# MDmotherboard.net
KiCad netlist of a schematic drawn in EAGLE
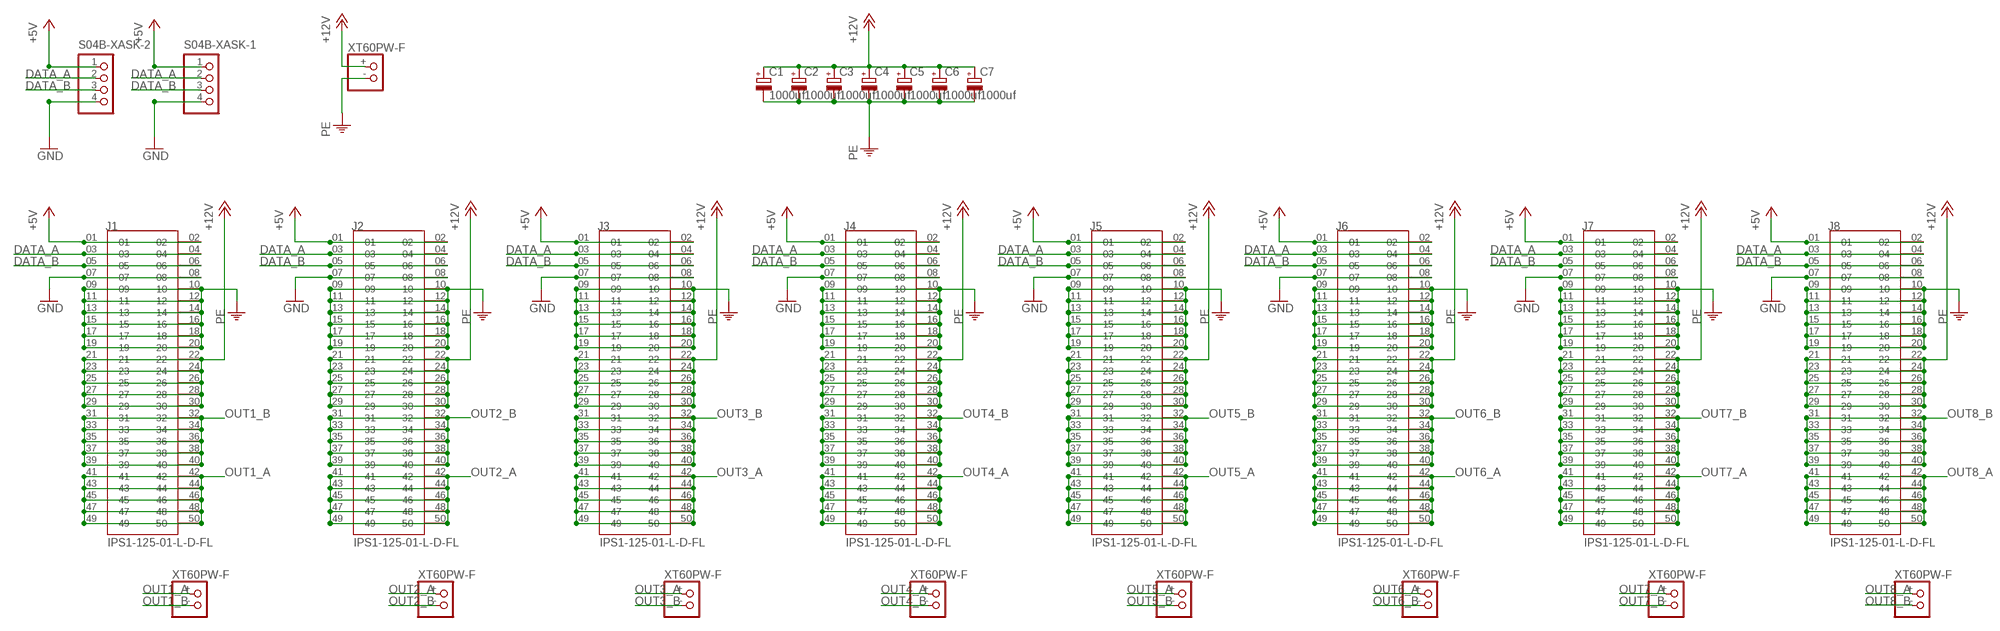
[diagram p0: schematic, sheet 1]

(export (version "E")
  (design (tool "Eeschema 10.0.6"))
  (components
    (comp (ref "C1")
      (value "1000uf")
      (footprint "eagle-import:E3,5-10")
      (libsource (lib "eagle-import") (part "CPOL-EUE3.5-10"))
    )
    (comp (ref "C2")
      (value "1000uf")
      (footprint "eagle-import:E3,5-10")
      (libsource (lib "eagle-import") (part "CPOL-EUE3.5-10"))
    )
    (comp (ref "C3")
      (value "1000uf")
      (footprint "eagle-import:E3,5-10")
      (libsource (lib "eagle-import") (part "CPOL-EUE3.5-10"))
    )
    (comp (ref "C4")
      (value "1000uf")
      (footprint "eagle-import:E3,5-10")
      (libsource (lib "eagle-import") (part "CPOL-EUE3.5-10"))
    )
    (comp (ref "C5")
      (value "1000uf")
      (footprint "eagle-import:E3,5-10")
      (libsource (lib "eagle-import") (part "CPOL-EUE3.5-10"))
    )
    (comp (ref "C6")
      (value "1000uf")
      (footprint "eagle-import:E3,5-10")
      (libsource (lib "eagle-import") (part "CPOL-EUE3.5-10"))
    )
    (comp (ref "C7")
      (value "1000uf")
      (footprint "eagle-import:E3,5-10")
      (libsource (lib "eagle-import") (part "CPOL-EUE3.5-10"))
    )
    (comp (ref "J1")
      (value "IPS1-125-01-L-D-FL")
      (footprint "eagle-import:SAMTEC_IPS1-125-01-L-D-FL")
      (fields (field (name "MF") "Samtec Inc."))
      (libsource (lib "eagle-import") (part "IPS1-125-01-L-D-FL"))
    )
    (comp (ref "J2")
      (value "IPS1-125-01-L-D-FL")
      (footprint "eagle-import:SAMTEC_IPS1-125-01-L-D-FL")
      (fields (field (name "MF") "Samtec Inc."))
      (libsource (lib "eagle-import") (part "IPS1-125-01-L-D-FL"))
    )
    (comp (ref "J3")
      (value "IPS1-125-01-L-D-FL")
      (footprint "eagle-import:SAMTEC_IPS1-125-01-L-D-FL")
      (fields (field (name "MF") "Samtec Inc."))
      (libsource (lib "eagle-import") (part "IPS1-125-01-L-D-FL"))
    )
    (comp (ref "J4")
      (value "IPS1-125-01-L-D-FL")
      (footprint "eagle-import:SAMTEC_IPS1-125-01-L-D-FL")
      (fields (field (name "MF") "Samtec Inc."))
      (libsource (lib "eagle-import") (part "IPS1-125-01-L-D-FL"))
    )
    (comp (ref "J5")
      (value "IPS1-125-01-L-D-FL")
      (footprint "eagle-import:SAMTEC_IPS1-125-01-L-D-FL")
      (fields (field (name "MF") "Samtec Inc."))
      (libsource (lib "eagle-import") (part "IPS1-125-01-L-D-FL"))
    )
    (comp (ref "J6")
      (value "IPS1-125-01-L-D-FL")
      (footprint "eagle-import:SAMTEC_IPS1-125-01-L-D-FL")
      (fields (field (name "MF") "Samtec Inc."))
      (libsource (lib "eagle-import") (part "IPS1-125-01-L-D-FL"))
    )
    (comp (ref "J7")
      (value "IPS1-125-01-L-D-FL")
      (footprint "eagle-import:SAMTEC_IPS1-125-01-L-D-FL")
      (fields (field (name "MF") "Samtec Inc."))
      (libsource (lib "eagle-import") (part "IPS1-125-01-L-D-FL"))
    )
    (comp (ref "J8")
      (value "IPS1-125-01-L-D-FL")
      (footprint "eagle-import:SAMTEC_IPS1-125-01-L-D-FL")
      (fields (field (name "MF") "Samtec Inc."))
      (libsource (lib "eagle-import") (part "IPS1-125-01-L-D-FL"))
    )
    (comp (ref "S04B-XASK-1")
      (value "S4B-XASK-1")
      (footprint "eagle-import:S4B-XASK-1")
      (libsource (lib "eagle-import") (part "S4B-XASK-1"))
    )
    (comp (ref "S04B-XASK-2")
      (value "S4B-XASK-1")
      (footprint "eagle-import:S4B-XASK-1")
      (libsource (lib "eagle-import") (part "S4B-XASK-1"))
    )
    (comp (ref "U$1")
      (value "XT60PW-F")
      (footprint "eagle-import:XT60PW-F")
      (libsource (lib "eagle-import") (part "XT60PW-F"))
    )
    (comp (ref "U$2")
      (value "XT60PW-F")
      (footprint "eagle-import:XT60PW-F")
      (libsource (lib "eagle-import") (part "XT60PW-F"))
    )
    (comp (ref "U$3")
      (value "XT60PW-F")
      (footprint "eagle-import:XT60PW-F")
      (libsource (lib "eagle-import") (part "XT60PW-F"))
    )
    (comp (ref "U$4")
      (value "XT60PW-F")
      (footprint "eagle-import:XT60PW-F")
      (libsource (lib "eagle-import") (part "XT60PW-F"))
    )
    (comp (ref "U$5")
      (value "XT60PW-F")
      (footprint "eagle-import:XT60PW-F")
      (libsource (lib "eagle-import") (part "XT60PW-F"))
    )
    (comp (ref "U$6")
      (value "XT60PW-F")
      (footprint "eagle-import:XT60PW-F")
      (libsource (lib "eagle-import") (part "XT60PW-F"))
    )
    (comp (ref "U$7")
      (value "XT60PW-F")
      (footprint "eagle-import:XT60PW-F")
      (libsource (lib "eagle-import") (part "XT60PW-F"))
    )
    (comp (ref "U$8")
      (value "XT60PW-F")
      (footprint "eagle-import:XT60PW-F")
      (libsource (lib "eagle-import") (part "XT60PW-F"))
    )
    (comp (ref "U$9")
      (value "XT60PW-F")
      (footprint "eagle-import:XT60PW-F")
      (libsource (lib "eagle-import") (part "XT60PW-F"))
    )
  )
  (nets
    (net (code "1") (name "+5V") (class "Default")
      (node (ref "J1") (pin "01") (pinfunction "01_01") (pintype "passive"))
      (node (ref "J1") (pin "02") (pinfunction "02_02") (pintype "passive"))
      (node (ref "J2") (pin "01") (pinfunction "01_01") (pintype "passive"))
      (node (ref "J2") (pin "02") (pinfunction "02_02") (pintype "passive"))
      (node (ref "J3") (pin "01") (pinfunction "01_01") (pintype "passive"))
      (node (ref "J3") (pin "02") (pinfunction "02_02") (pintype "passive"))
      (node (ref "J4") (pin "01") (pinfunction "01_01") (pintype "passive"))
      (node (ref "J4") (pin "02") (pinfunction "02_02") (pintype "passive"))
      (node (ref "J5") (pin "01") (pinfunction "01_01") (pintype "passive"))
      (node (ref "J5") (pin "02") (pinfunction "02_02") (pintype "passive"))
      (node (ref "J6") (pin "01") (pinfunction "01_01") (pintype "passive"))
      (node (ref "J6") (pin "02") (pinfunction "02_02") (pintype "passive"))
      (node (ref "J7") (pin "01") (pinfunction "01_01") (pintype "passive"))
      (node (ref "J7") (pin "02") (pinfunction "02_02") (pintype "passive"))
      (node (ref "J8") (pin "01") (pinfunction "01_01") (pintype "passive"))
      (node (ref "J8") (pin "02") (pinfunction "02_02") (pintype "passive"))
      (node (ref "S04B-XASK-1") (pin "1") (pinfunction "1_1") (pintype "passive"))
      (node (ref "S04B-XASK-2") (pin "1") (pinfunction "1_1") (pintype "passive"))
    )
    (net (code "2") (name "+12V") (class "Default")
      (node (ref "C1") (pin "+") (pinfunction "+_+") (pintype "passive"))
      (node (ref "C2") (pin "+") (pinfunction "+_+") (pintype "passive"))
      (node (ref "C3") (pin "+") (pinfunction "+_+") (pintype "passive"))
      (node (ref "C4") (pin "+") (pinfunction "+_+") (pintype "passive"))
      (node (ref "C5") (pin "+") (pinfunction "+_+") (pintype "passive"))
      (node (ref "C6") (pin "+") (pinfunction "+_+") (pintype "passive"))
      (node (ref "C7") (pin "+") (pinfunction "+_+") (pintype "passive"))
      (node (ref "J1") (pin "21") (pinfunction "21_21") (pintype "passive"))
      (node (ref "J1") (pin "22") (pinfunction "22_22") (pintype "passive"))
      (node (ref "J1") (pin "23") (pinfunction "23_23") (pintype "passive"))
      (node (ref "J1") (pin "24") (pinfunction "24_24") (pintype "passive"))
      (node (ref "J1") (pin "25") (pinfunction "25_25") (pintype "passive"))
      (node (ref "J1") (pin "26") (pinfunction "26_26") (pintype "passive"))
      (node (ref "J1") (pin "27") (pinfunction "27_27") (pintype "passive"))
      (node (ref "J1") (pin "28") (pinfunction "28_28") (pintype "passive"))
      (node (ref "J1") (pin "29") (pinfunction "29_29") (pintype "passive"))
      (node (ref "J1") (pin "30") (pinfunction "30_30") (pintype "passive"))
      (node (ref "J2") (pin "21") (pinfunction "21_21") (pintype "passive"))
      (node (ref "J2") (pin "22") (pinfunction "22_22") (pintype "passive"))
      (node (ref "J2") (pin "23") (pinfunction "23_23") (pintype "passive"))
      (node (ref "J2") (pin "24") (pinfunction "24_24") (pintype "passive"))
      (node (ref "J2") (pin "25") (pinfunction "25_25") (pintype "passive"))
      (node (ref "J2") (pin "26") (pinfunction "26_26") (pintype "passive"))
      (node (ref "J2") (pin "27") (pinfunction "27_27") (pintype "passive"))
      (node (ref "J2") (pin "28") (pinfunction "28_28") (pintype "passive"))
      (node (ref "J2") (pin "29") (pinfunction "29_29") (pintype "passive"))
      (node (ref "J2") (pin "30") (pinfunction "30_30") (pintype "passive"))
      (node (ref "J3") (pin "21") (pinfunction "21_21") (pintype "passive"))
      (node (ref "J3") (pin "22") (pinfunction "22_22") (pintype "passive"))
      (node (ref "J3") (pin "23") (pinfunction "23_23") (pintype "passive"))
      (node (ref "J3") (pin "24") (pinfunction "24_24") (pintype "passive"))
      (node (ref "J3") (pin "25") (pinfunction "25_25") (pintype "passive"))
      (node (ref "J3") (pin "26") (pinfunction "26_26") (pintype "passive"))
      (node (ref "J3") (pin "27") (pinfunction "27_27") (pintype "passive"))
      (node (ref "J3") (pin "28") (pinfunction "28_28") (pintype "passive"))
      (node (ref "J3") (pin "29") (pinfunction "29_29") (pintype "passive"))
      (node (ref "J3") (pin "30") (pinfunction "30_30") (pintype "passive"))
      (node (ref "J4") (pin "21") (pinfunction "21_21") (pintype "passive"))
      (node (ref "J4") (pin "22") (pinfunction "22_22") (pintype "passive"))
      (node (ref "J4") (pin "23") (pinfunction "23_23") (pintype "passive"))
      (node (ref "J4") (pin "24") (pinfunction "24_24") (pintype "passive"))
      (node (ref "J4") (pin "25") (pinfunction "25_25") (pintype "passive"))
      (node (ref "J4") (pin "26") (pinfunction "26_26") (pintype "passive"))
      (node (ref "J4") (pin "27") (pinfunction "27_27") (pintype "passive"))
      (node (ref "J4") (pin "28") (pinfunction "28_28") (pintype "passive"))
      (node (ref "J4") (pin "29") (pinfunction "29_29") (pintype "passive"))
      (node (ref "J4") (pin "30") (pinfunction "30_30") (pintype "passive"))
      (node (ref "J5") (pin "21") (pinfunction "21_21") (pintype "passive"))
      (node (ref "J5") (pin "22") (pinfunction "22_22") (pintype "passive"))
      (node (ref "J5") (pin "23") (pinfunction "23_23") (pintype "passive"))
      (node (ref "J5") (pin "24") (pinfunction "24_24") (pintype "passive"))
      (node (ref "J5") (pin "25") (pinfunction "25_25") (pintype "passive"))
      (node (ref "J5") (pin "26") (pinfunction "26_26") (pintype "passive"))
      (node (ref "J5") (pin "27") (pinfunction "27_27") (pintype "passive"))
      (node (ref "J5") (pin "28") (pinfunction "28_28") (pintype "passive"))
      (node (ref "J5") (pin "29") (pinfunction "29_29") (pintype "passive"))
      (node (ref "J5") (pin "30") (pinfunction "30_30") (pintype "passive"))
      (node (ref "J6") (pin "21") (pinfunction "21_21") (pintype "passive"))
      (node (ref "J6") (pin "22") (pinfunction "22_22") (pintype "passive"))
      (node (ref "J6") (pin "23") (pinfunction "23_23") (pintype "passive"))
      (node (ref "J6") (pin "24") (pinfunction "24_24") (pintype "passive"))
      (node (ref "J6") (pin "25") (pinfunction "25_25") (pintype "passive"))
      (node (ref "J6") (pin "26") (pinfunction "26_26") (pintype "passive"))
      (node (ref "J6") (pin "27") (pinfunction "27_27") (pintype "passive"))
      (node (ref "J6") (pin "28") (pinfunction "28_28") (pintype "passive"))
      (node (ref "J6") (pin "29") (pinfunction "29_29") (pintype "passive"))
      (node (ref "J6") (pin "30") (pinfunction "30_30") (pintype "passive"))
      (node (ref "J7") (pin "21") (pinfunction "21_21") (pintype "passive"))
      (node (ref "J7") (pin "22") (pinfunction "22_22") (pintype "passive"))
      (node (ref "J7") (pin "23") (pinfunction "23_23") (pintype "passive"))
      (node (ref "J7") (pin "24") (pinfunction "24_24") (pintype "passive"))
      (node (ref "J7") (pin "25") (pinfunction "25_25") (pintype "passive"))
      (node (ref "J7") (pin "26") (pinfunction "26_26") (pintype "passive"))
      (node (ref "J7") (pin "27") (pinfunction "27_27") (pintype "passive"))
      (node (ref "J7") (pin "28") (pinfunction "28_28") (pintype "passive"))
      (node (ref "J7") (pin "29") (pinfunction "29_29") (pintype "passive"))
      (node (ref "J7") (pin "30") (pinfunction "30_30") (pintype "passive"))
      (node (ref "J8") (pin "21") (pinfunction "21_21") (pintype "passive"))
      (node (ref "J8") (pin "22") (pinfunction "22_22") (pintype "passive"))
      (node (ref "J8") (pin "23") (pinfunction "23_23") (pintype "passive"))
      (node (ref "J8") (pin "24") (pinfunction "24_24") (pintype "passive"))
      (node (ref "J8") (pin "25") (pinfunction "25_25") (pintype "passive"))
      (node (ref "J8") (pin "26") (pinfunction "26_26") (pintype "passive"))
      (node (ref "J8") (pin "27") (pinfunction "27_27") (pintype "passive"))
      (node (ref "J8") (pin "28") (pinfunction "28_28") (pintype "passive"))
      (node (ref "J8") (pin "29") (pinfunction "29_29") (pintype "passive"))
      (node (ref "J8") (pin "30") (pinfunction "30_30") (pintype "passive"))
      (node (ref "U$1") (pin "+") (pinfunction "+_+") (pintype "passive"))
    )
    (net (code "3") (name "/DATA_A") (class "Default")
      (node (ref "J1") (pin "03") (pinfunction "03_03") (pintype "passive"))
      (node (ref "J1") (pin "04") (pinfunction "04_04") (pintype "passive"))
      (node (ref "J2") (pin "03") (pinfunction "03_03") (pintype "passive"))
      (node (ref "J2") (pin "04") (pinfunction "04_04") (pintype "passive"))
      (node (ref "J3") (pin "03") (pinfunction "03_03") (pintype "passive"))
      (node (ref "J3") (pin "04") (pinfunction "04_04") (pintype "passive"))
      (node (ref "J4") (pin "03") (pinfunction "03_03") (pintype "passive"))
      (node (ref "J4") (pin "04") (pinfunction "04_04") (pintype "passive"))
      (node (ref "J5") (pin "03") (pinfunction "03_03") (pintype "passive"))
      (node (ref "J5") (pin "04") (pinfunction "04_04") (pintype "passive"))
      (node (ref "J6") (pin "03") (pinfunction "03_03") (pintype "passive"))
      (node (ref "J6") (pin "04") (pinfunction "04_04") (pintype "passive"))
      (node (ref "J7") (pin "03") (pinfunction "03_03") (pintype "passive"))
      (node (ref "J7") (pin "04") (pinfunction "04_04") (pintype "passive"))
      (node (ref "J8") (pin "03") (pinfunction "03_03") (pintype "passive"))
      (node (ref "J8") (pin "04") (pinfunction "04_04") (pintype "passive"))
      (node (ref "S04B-XASK-1") (pin "2") (pinfunction "2_2") (pintype "passive"))
      (node (ref "S04B-XASK-2") (pin "2") (pinfunction "2_2") (pintype "passive"))
    )
    (net (code "4") (name "/DATA_B") (class "Default")
      (node (ref "J1") (pin "05") (pinfunction "05_05") (pintype "passive"))
      (node (ref "J1") (pin "06") (pinfunction "06_06") (pintype "passive"))
      (node (ref "J2") (pin "05") (pinfunction "05_05") (pintype "passive"))
      (node (ref "J2") (pin "06") (pinfunction "06_06") (pintype "passive"))
      (node (ref "J3") (pin "05") (pinfunction "05_05") (pintype "passive"))
      (node (ref "J3") (pin "06") (pinfunction "06_06") (pintype "passive"))
      (node (ref "J4") (pin "05") (pinfunction "05_05") (pintype "passive"))
      (node (ref "J4") (pin "06") (pinfunction "06_06") (pintype "passive"))
      (node (ref "J5") (pin "05") (pinfunction "05_05") (pintype "passive"))
      (node (ref "J5") (pin "06") (pinfunction "06_06") (pintype "passive"))
      (node (ref "J6") (pin "05") (pinfunction "05_05") (pintype "passive"))
      (node (ref "J6") (pin "06") (pinfunction "06_06") (pintype "passive"))
      (node (ref "J7") (pin "05") (pinfunction "05_05") (pintype "passive"))
      (node (ref "J7") (pin "06") (pinfunction "06_06") (pintype "passive"))
      (node (ref "J8") (pin "05") (pinfunction "05_05") (pintype "passive"))
      (node (ref "J8") (pin "06") (pinfunction "06_06") (pintype "passive"))
      (node (ref "S04B-XASK-1") (pin "3") (pinfunction "3_3") (pintype "passive"))
      (node (ref "S04B-XASK-2") (pin "3") (pinfunction "3_3") (pintype "passive"))
    )
    (net (code "5") (name "/OUT1_A") (class "Default")
      (node (ref "J1") (pin "41") (pinfunction "41_41") (pintype "passive"))
      (node (ref "J1") (pin "42") (pinfunction "42_42") (pintype "passive"))
      (node (ref "J1") (pin "43") (pinfunction "43_43") (pintype "passive"))
      (node (ref "J1") (pin "44") (pinfunction "44_44") (pintype "passive"))
      (node (ref "J1") (pin "45") (pinfunction "45_45") (pintype "passive"))
      (node (ref "J1") (pin "46") (pinfunction "46_46") (pintype "passive"))
      (node (ref "J1") (pin "47") (pinfunction "47_47") (pintype "passive"))
      (node (ref "J1") (pin "48") (pinfunction "48_48") (pintype "passive"))
      (node (ref "J1") (pin "49") (pinfunction "49_49") (pintype "passive"))
      (node (ref "J1") (pin "50") (pinfunction "50_50") (pintype "passive"))
      (node (ref "U$2") (pin "+") (pinfunction "+_+") (pintype "passive"))
    )
    (net (code "6") (name "/OUT1_B") (class "Default")
      (node (ref "J1") (pin "31") (pinfunction "31_31") (pintype "passive"))
      (node (ref "J1") (pin "32") (pinfunction "32_32") (pintype "passive"))
      (node (ref "J1") (pin "33") (pinfunction "33_33") (pintype "passive"))
      (node (ref "J1") (pin "34") (pinfunction "34_34") (pintype "passive"))
      (node (ref "J1") (pin "35") (pinfunction "35_35") (pintype "passive"))
      (node (ref "J1") (pin "36") (pinfunction "36_36") (pintype "passive"))
      (node (ref "J1") (pin "37") (pinfunction "37_37") (pintype "passive"))
      (node (ref "J1") (pin "38") (pinfunction "38_38") (pintype "passive"))
      (node (ref "J1") (pin "39") (pinfunction "39_39") (pintype "passive"))
      (node (ref "J1") (pin "40") (pinfunction "40_40") (pintype "passive"))
      (node (ref "U$2") (pin "-") (pinfunction "-_-") (pintype "passive"))
    )
    (net (code "7") (name "/OUT2_A") (class "Default")
      (node (ref "J2") (pin "41") (pinfunction "41_41") (pintype "passive"))
      (node (ref "J2") (pin "42") (pinfunction "42_42") (pintype "passive"))
      (node (ref "J2") (pin "43") (pinfunction "43_43") (pintype "passive"))
      (node (ref "J2") (pin "44") (pinfunction "44_44") (pintype "passive"))
      (node (ref "J2") (pin "45") (pinfunction "45_45") (pintype "passive"))
      (node (ref "J2") (pin "46") (pinfunction "46_46") (pintype "passive"))
      (node (ref "J2") (pin "47") (pinfunction "47_47") (pintype "passive"))
      (node (ref "J2") (pin "48") (pinfunction "48_48") (pintype "passive"))
      (node (ref "J2") (pin "49") (pinfunction "49_49") (pintype "passive"))
      (node (ref "J2") (pin "50") (pinfunction "50_50") (pintype "passive"))
      (node (ref "U$3") (pin "+") (pinfunction "+_+") (pintype "passive"))
    )
    (net (code "8") (name "/OUT2_B") (class "Default")
      (node (ref "J2") (pin "31") (pinfunction "31_31") (pintype "passive"))
      (node (ref "J2") (pin "32") (pinfunction "32_32") (pintype "passive"))
      (node (ref "J2") (pin "33") (pinfunction "33_33") (pintype "passive"))
      (node (ref "J2") (pin "34") (pinfunction "34_34") (pintype "passive"))
      (node (ref "J2") (pin "35") (pinfunction "35_35") (pintype "passive"))
      (node (ref "J2") (pin "36") (pinfunction "36_36") (pintype "passive"))
      (node (ref "J2") (pin "37") (pinfunction "37_37") (pintype "passive"))
      (node (ref "J2") (pin "38") (pinfunction "38_38") (pintype "passive"))
      (node (ref "J2") (pin "39") (pinfunction "39_39") (pintype "passive"))
      (node (ref "J2") (pin "40") (pinfunction "40_40") (pintype "passive"))
      (node (ref "U$3") (pin "-") (pinfunction "-_-") (pintype "passive"))
    )
    (net (code "9") (name "/OUT3_A") (class "Default")
      (node (ref "J3") (pin "41") (pinfunction "41_41") (pintype "passive"))
      (node (ref "J3") (pin "42") (pinfunction "42_42") (pintype "passive"))
      (node (ref "J3") (pin "43") (pinfunction "43_43") (pintype "passive"))
      (node (ref "J3") (pin "44") (pinfunction "44_44") (pintype "passive"))
      (node (ref "J3") (pin "45") (pinfunction "45_45") (pintype "passive"))
      (node (ref "J3") (pin "46") (pinfunction "46_46") (pintype "passive"))
      (node (ref "J3") (pin "47") (pinfunction "47_47") (pintype "passive"))
      (node (ref "J3") (pin "48") (pinfunction "48_48") (pintype "passive"))
      (node (ref "J3") (pin "49") (pinfunction "49_49") (pintype "passive"))
      (node (ref "J3") (pin "50") (pinfunction "50_50") (pintype "passive"))
      (node (ref "U$4") (pin "+") (pinfunction "+_+") (pintype "passive"))
    )
    (net (code "10") (name "/OUT3_B") (class "Default")
      (node (ref "J3") (pin "31") (pinfunction "31_31") (pintype "passive"))
      (node (ref "J3") (pin "32") (pinfunction "32_32") (pintype "passive"))
      (node (ref "J3") (pin "33") (pinfunction "33_33") (pintype "passive"))
      (node (ref "J3") (pin "34") (pinfunction "34_34") (pintype "passive"))
      (node (ref "J3") (pin "35") (pinfunction "35_35") (pintype "passive"))
      (node (ref "J3") (pin "36") (pinfunction "36_36") (pintype "passive"))
      (node (ref "J3") (pin "37") (pinfunction "37_37") (pintype "passive"))
      (node (ref "J3") (pin "38") (pinfunction "38_38") (pintype "passive"))
      (node (ref "J3") (pin "39") (pinfunction "39_39") (pintype "passive"))
      (node (ref "J3") (pin "40") (pinfunction "40_40") (pintype "passive"))
      (node (ref "U$4") (pin "-") (pinfunction "-_-") (pintype "passive"))
    )
    (net (code "11") (name "/OUT4_A") (class "Default")
      (node (ref "J4") (pin "41") (pinfunction "41_41") (pintype "passive"))
      (node (ref "J4") (pin "42") (pinfunction "42_42") (pintype "passive"))
      (node (ref "J4") (pin "43") (pinfunction "43_43") (pintype "passive"))
      (node (ref "J4") (pin "44") (pinfunction "44_44") (pintype "passive"))
      (node (ref "J4") (pin "45") (pinfunction "45_45") (pintype "passive"))
      (node (ref "J4") (pin "46") (pinfunction "46_46") (pintype "passive"))
      (node (ref "J4") (pin "47") (pinfunction "47_47") (pintype "passive"))
      (node (ref "J4") (pin "48") (pinfunction "48_48") (pintype "passive"))
      (node (ref "J4") (pin "49") (pinfunction "49_49") (pintype "passive"))
      (node (ref "J4") (pin "50") (pinfunction "50_50") (pintype "passive"))
      (node (ref "U$5") (pin "+") (pinfunction "+_+") (pintype "passive"))
    )
    (net (code "12") (name "/OUT4_B") (class "Default")
      (node (ref "J4") (pin "31") (pinfunction "31_31") (pintype "passive"))
      (node (ref "J4") (pin "32") (pinfunction "32_32") (pintype "passive"))
      (node (ref "J4") (pin "33") (pinfunction "33_33") (pintype "passive"))
      (node (ref "J4") (pin "34") (pinfunction "34_34") (pintype "passive"))
      (node (ref "J4") (pin "35") (pinfunction "35_35") (pintype "passive"))
      (node (ref "J4") (pin "36") (pinfunction "36_36") (pintype "passive"))
      (node (ref "J4") (pin "37") (pinfunction "37_37") (pintype "passive"))
      (node (ref "J4") (pin "38") (pinfunction "38_38") (pintype "passive"))
      (node (ref "J4") (pin "39") (pinfunction "39_39") (pintype "passive"))
      (node (ref "J4") (pin "40") (pinfunction "40_40") (pintype "passive"))
      (node (ref "U$5") (pin "-") (pinfunction "-_-") (pintype "passive"))
    )
    (net (code "13") (name "/OUT5_A") (class "Default")
      (node (ref "J5") (pin "41") (pinfunction "41_41") (pintype "passive"))
      (node (ref "J5") (pin "42") (pinfunction "42_42") (pintype "passive"))
      (node (ref "J5") (pin "43") (pinfunction "43_43") (pintype "passive"))
      (node (ref "J5") (pin "44") (pinfunction "44_44") (pintype "passive"))
      (node (ref "J5") (pin "45") (pinfunction "45_45") (pintype "passive"))
      (node (ref "J5") (pin "46") (pinfunction "46_46") (pintype "passive"))
      (node (ref "J5") (pin "47") (pinfunction "47_47") (pintype "passive"))
      (node (ref "J5") (pin "48") (pinfunction "48_48") (pintype "passive"))
      (node (ref "J5") (pin "49") (pinfunction "49_49") (pintype "passive"))
      (node (ref "J5") (pin "50") (pinfunction "50_50") (pintype "passive"))
      (node (ref "U$6") (pin "+") (pinfunction "+_+") (pintype "passive"))
    )
    (net (code "14") (name "/OUT5_B") (class "Default")
      (node (ref "J5") (pin "31") (pinfunction "31_31") (pintype "passive"))
      (node (ref "J5") (pin "32") (pinfunction "32_32") (pintype "passive"))
      (node (ref "J5") (pin "33") (pinfunction "33_33") (pintype "passive"))
      (node (ref "J5") (pin "34") (pinfunction "34_34") (pintype "passive"))
      (node (ref "J5") (pin "35") (pinfunction "35_35") (pintype "passive"))
      (node (ref "J5") (pin "36") (pinfunction "36_36") (pintype "passive"))
      (node (ref "J5") (pin "37") (pinfunction "37_37") (pintype "passive"))
      (node (ref "J5") (pin "38") (pinfunction "38_38") (pintype "passive"))
      (node (ref "J5") (pin "39") (pinfunction "39_39") (pintype "passive"))
      (node (ref "J5") (pin "40") (pinfunction "40_40") (pintype "passive"))
      (node (ref "U$6") (pin "-") (pinfunction "-_-") (pintype "passive"))
    )
    (net (code "15") (name "/OUT6_A") (class "Default")
      (node (ref "J6") (pin "41") (pinfunction "41_41") (pintype "passive"))
      (node (ref "J6") (pin "42") (pinfunction "42_42") (pintype "passive"))
      (node (ref "J6") (pin "43") (pinfunction "43_43") (pintype "passive"))
      (node (ref "J6") (pin "44") (pinfunction "44_44") (pintype "passive"))
      (node (ref "J6") (pin "45") (pinfunction "45_45") (pintype "passive"))
      (node (ref "J6") (pin "46") (pinfunction "46_46") (pintype "passive"))
      (node (ref "J6") (pin "47") (pinfunction "47_47") (pintype "passive"))
      (node (ref "J6") (pin "48") (pinfunction "48_48") (pintype "passive"))
      (node (ref "J6") (pin "49") (pinfunction "49_49") (pintype "passive"))
      (node (ref "J6") (pin "50") (pinfunction "50_50") (pintype "passive"))
      (node (ref "U$7") (pin "+") (pinfunction "+_+") (pintype "passive"))
    )
    (net (code "16") (name "/OUT6_B") (class "Default")
      (node (ref "J6") (pin "31") (pinfunction "31_31") (pintype "passive"))
      (node (ref "J6") (pin "32") (pinfunction "32_32") (pintype "passive"))
      (node (ref "J6") (pin "33") (pinfunction "33_33") (pintype "passive"))
      (node (ref "J6") (pin "34") (pinfunction "34_34") (pintype "passive"))
      (node (ref "J6") (pin "35") (pinfunction "35_35") (pintype "passive"))
      (node (ref "J6") (pin "36") (pinfunction "36_36") (pintype "passive"))
      (node (ref "J6") (pin "37") (pinfunction "37_37") (pintype "passive"))
      (node (ref "J6") (pin "38") (pinfunction "38_38") (pintype "passive"))
      (node (ref "J6") (pin "39") (pinfunction "39_39") (pintype "passive"))
      (node (ref "J6") (pin "40") (pinfunction "40_40") (pintype "passive"))
      (node (ref "U$7") (pin "-") (pinfunction "-_-") (pintype "passive"))
    )
    (net (code "17") (name "/OUT7_A") (class "Default")
      (node (ref "J7") (pin "41") (pinfunction "41_41") (pintype "passive"))
      (node (ref "J7") (pin "42") (pinfunction "42_42") (pintype "passive"))
      (node (ref "J7") (pin "43") (pinfunction "43_43") (pintype "passive"))
      (node (ref "J7") (pin "44") (pinfunction "44_44") (pintype "passive"))
      (node (ref "J7") (pin "45") (pinfunction "45_45") (pintype "passive"))
      (node (ref "J7") (pin "46") (pinfunction "46_46") (pintype "passive"))
      (node (ref "J7") (pin "47") (pinfunction "47_47") (pintype "passive"))
      (node (ref "J7") (pin "48") (pinfunction "48_48") (pintype "passive"))
      (node (ref "J7") (pin "49") (pinfunction "49_49") (pintype "passive"))
      (node (ref "J7") (pin "50") (pinfunction "50_50") (pintype "passive"))
      (node (ref "U$8") (pin "+") (pinfunction "+_+") (pintype "passive"))
    )
    (net (code "18") (name "/OUT7_B") (class "Default")
      (node (ref "J7") (pin "31") (pinfunction "31_31") (pintype "passive"))
      (node (ref "J7") (pin "32") (pinfunction "32_32") (pintype "passive"))
      (node (ref "J7") (pin "33") (pinfunction "33_33") (pintype "passive"))
      (node (ref "J7") (pin "34") (pinfunction "34_34") (pintype "passive"))
      (node (ref "J7") (pin "35") (pinfunction "35_35") (pintype "passive"))
      (node (ref "J7") (pin "36") (pinfunction "36_36") (pintype "passive"))
      (node (ref "J7") (pin "37") (pinfunction "37_37") (pintype "passive"))
      (node (ref "J7") (pin "38") (pinfunction "38_38") (pintype "passive"))
      (node (ref "J7") (pin "39") (pinfunction "39_39") (pintype "passive"))
      (node (ref "J7") (pin "40") (pinfunction "40_40") (pintype "passive"))
      (node (ref "U$8") (pin "-") (pinfunction "-_-") (pintype "passive"))
    )
    (net (code "19") (name "/OUT8_A") (class "Default")
      (node (ref "J8") (pin "41") (pinfunction "41_41") (pintype "passive"))
      (node (ref "J8") (pin "42") (pinfunction "42_42") (pintype "passive"))
      (node (ref "J8") (pin "43") (pinfunction "43_43") (pintype "passive"))
      (node (ref "J8") (pin "44") (pinfunction "44_44") (pintype "passive"))
      (node (ref "J8") (pin "45") (pinfunction "45_45") (pintype "passive"))
      (node (ref "J8") (pin "46") (pinfunction "46_46") (pintype "passive"))
      (node (ref "J8") (pin "47") (pinfunction "47_47") (pintype "passive"))
      (node (ref "J8") (pin "48") (pinfunction "48_48") (pintype "passive"))
      (node (ref "J8") (pin "49") (pinfunction "49_49") (pintype "passive"))
      (node (ref "J8") (pin "50") (pinfunction "50_50") (pintype "passive"))
      (node (ref "U$9") (pin "+") (pinfunction "+_+") (pintype "passive"))
    )
    (net (code "20") (name "/OUT8_B") (class "Default")
      (node (ref "J8") (pin "31") (pinfunction "31_31") (pintype "passive"))
      (node (ref "J8") (pin "32") (pinfunction "32_32") (pintype "passive"))
      (node (ref "J8") (pin "33") (pinfunction "33_33") (pintype "passive"))
      (node (ref "J8") (pin "34") (pinfunction "34_34") (pintype "passive"))
      (node (ref "J8") (pin "35") (pinfunction "35_35") (pintype "passive"))
      (node (ref "J8") (pin "36") (pinfunction "36_36") (pintype "passive"))
      (node (ref "J8") (pin "37") (pinfunction "37_37") (pintype "passive"))
      (node (ref "J8") (pin "38") (pinfunction "38_38") (pintype "passive"))
      (node (ref "J8") (pin "39") (pinfunction "39_39") (pintype "passive"))
      (node (ref "J8") (pin "40") (pinfunction "40_40") (pintype "passive"))
      (node (ref "U$9") (pin "-") (pinfunction "-_-") (pintype "passive"))
    )
    (net (code "21") (name "GND") (class "Default")
      (node (ref "J1") (pin "07") (pinfunction "07_07") (pintype "passive"))
      (node (ref "J1") (pin "08") (pinfunction "08_08") (pintype "passive"))
      (node (ref "J2") (pin "07") (pinfunction "07_07") (pintype "passive"))
      (node (ref "J2") (pin "08") (pinfunction "08_08") (pintype "passive"))
      (node (ref "J3") (pin "07") (pinfunction "07_07") (pintype "passive"))
      (node (ref "J3") (pin "08") (pinfunction "08_08") (pintype "passive"))
      (node (ref "J4") (pin "07") (pinfunction "07_07") (pintype "passive"))
      (node (ref "J4") (pin "08") (pinfunction "08_08") (pintype "passive"))
      (node (ref "J5") (pin "07") (pinfunction "07_07") (pintype "passive"))
      (node (ref "J5") (pin "08") (pinfunction "08_08") (pintype "passive"))
      (node (ref "J6") (pin "07") (pinfunction "07_07") (pintype "passive"))
      (node (ref "J6") (pin "08") (pinfunction "08_08") (pintype "passive"))
      (node (ref "J7") (pin "07") (pinfunction "07_07") (pintype "passive"))
      (node (ref "J7") (pin "08") (pinfunction "08_08") (pintype "passive"))
      (node (ref "J8") (pin "07") (pinfunction "07_07") (pintype "passive"))
      (node (ref "J8") (pin "08") (pinfunction "08_08") (pintype "passive"))
      (node (ref "S04B-XASK-1") (pin "4") (pinfunction "4_4") (pintype "passive"))
      (node (ref "S04B-XASK-2") (pin "4") (pinfunction "4_4") (pintype "passive"))
    )
    (net (code "22") (name "PE") (class "Default")
      (node (ref "C1") (pin "-") (pinfunction "-_-") (pintype "passive"))
      (node (ref "C2") (pin "-") (pinfunction "-_-") (pintype "passive"))
      (node (ref "C3") (pin "-") (pinfunction "-_-") (pintype "passive"))
      (node (ref "C4") (pin "-") (pinfunction "-_-") (pintype "passive"))
      (node (ref "C5") (pin "-") (pinfunction "-_-") (pintype "passive"))
      (node (ref "C6") (pin "-") (pinfunction "-_-") (pintype "passive"))
      (node (ref "C7") (pin "-") (pinfunction "-_-") (pintype "passive"))
      (node (ref "J1") (pin "09") (pinfunction "09_09") (pintype "passive"))
      (node (ref "J1") (pin "10") (pinfunction "10_10") (pintype "passive"))
      (node (ref "J1") (pin "11") (pinfunction "11_11") (pintype "passive"))
      (node (ref "J1") (pin "12") (pinfunction "12_12") (pintype "passive"))
      (node (ref "J1") (pin "13") (pinfunction "13_13") (pintype "passive"))
      (node (ref "J1") (pin "14") (pinfunction "14_14") (pintype "passive"))
      (node (ref "J1") (pin "15") (pinfunction "15_15") (pintype "passive"))
      (node (ref "J1") (pin "16") (pinfunction "16_16") (pintype "passive"))
      (node (ref "J1") (pin "17") (pinfunction "17_17") (pintype "passive"))
      (node (ref "J1") (pin "18") (pinfunction "18_18") (pintype "passive"))
      (node (ref "J1") (pin "19") (pinfunction "19_19") (pintype "passive"))
      (node (ref "J1") (pin "20") (pinfunction "20_20") (pintype "passive"))
      (node (ref "J2") (pin "09") (pinfunction "09_09") (pintype "passive"))
      (node (ref "J2") (pin "10") (pinfunction "10_10") (pintype "passive"))
      (node (ref "J2") (pin "11") (pinfunction "11_11") (pintype "passive"))
      (node (ref "J2") (pin "12") (pinfunction "12_12") (pintype "passive"))
      (node (ref "J2") (pin "13") (pinfunction "13_13") (pintype "passive"))
      (node (ref "J2") (pin "14") (pinfunction "14_14") (pintype "passive"))
      (node (ref "J2") (pin "15") (pinfunction "15_15") (pintype "passive"))
      (node (ref "J2") (pin "16") (pinfunction "16_16") (pintype "passive"))
      (node (ref "J2") (pin "17") (pinfunction "17_17") (pintype "passive"))
      (node (ref "J2") (pin "18") (pinfunction "18_18") (pintype "passive"))
      (node (ref "J2") (pin "19") (pinfunction "19_19") (pintype "passive"))
      (node (ref "J2") (pin "20") (pinfunction "20_20") (pintype "passive"))
      (node (ref "J3") (pin "09") (pinfunction "09_09") (pintype "passive"))
      (node (ref "J3") (pin "10") (pinfunction "10_10") (pintype "passive"))
      (node (ref "J3") (pin "11") (pinfunction "11_11") (pintype "passive"))
      (node (ref "J3") (pin "12") (pinfunction "12_12") (pintype "passive"))
      (node (ref "J3") (pin "13") (pinfunction "13_13") (pintype "passive"))
      (node (ref "J3") (pin "14") (pinfunction "14_14") (pintype "passive"))
      (node (ref "J3") (pin "15") (pinfunction "15_15") (pintype "passive"))
      (node (ref "J3") (pin "16") (pinfunction "16_16") (pintype "passive"))
      (node (ref "J3") (pin "17") (pinfunction "17_17") (pintype "passive"))
      (node (ref "J3") (pin "18") (pinfunction "18_18") (pintype "passive"))
      (node (ref "J3") (pin "19") (pinfunction "19_19") (pintype "passive"))
      (node (ref "J3") (pin "20") (pinfunction "20_20") (pintype "passive"))
      (node (ref "J4") (pin "09") (pinfunction "09_09") (pintype "passive"))
      (node (ref "J4") (pin "10") (pinfunction "10_10") (pintype "passive"))
      (node (ref "J4") (pin "11") (pinfunction "11_11") (pintype "passive"))
      (node (ref "J4") (pin "12") (pinfunction "12_12") (pintype "passive"))
      (node (ref "J4") (pin "13") (pinfunction "13_13") (pintype "passive"))
      (node (ref "J4") (pin "14") (pinfunction "14_14") (pintype "passive"))
      (node (ref "J4") (pin "15") (pinfunction "15_15") (pintype "passive"))
      (node (ref "J4") (pin "16") (pinfunction "16_16") (pintype "passive"))
      (node (ref "J4") (pin "17") (pinfunction "17_17") (pintype "passive"))
      (node (ref "J4") (pin "18") (pinfunction "18_18") (pintype "passive"))
      (node (ref "J4") (pin "19") (pinfunction "19_19") (pintype "passive"))
      (node (ref "J4") (pin "20") (pinfunction "20_20") (pintype "passive"))
      (node (ref "J5") (pin "09") (pinfunction "09_09") (pintype "passive"))
      (node (ref "J5") (pin "10") (pinfunction "10_10") (pintype "passive"))
      (node (ref "J5") (pin "11") (pinfunction "11_11") (pintype "passive"))
      (node (ref "J5") (pin "12") (pinfunction "12_12") (pintype "passive"))
      (node (ref "J5") (pin "13") (pinfunction "13_13") (pintype "passive"))
      (node (ref "J5") (pin "14") (pinfunction "14_14") (pintype "passive"))
      (node (ref "J5") (pin "15") (pinfunction "15_15") (pintype "passive"))
      (node (ref "J5") (pin "16") (pinfunction "16_16") (pintype "passive"))
      (node (ref "J5") (pin "17") (pinfunction "17_17") (pintype "passive"))
      (node (ref "J5") (pin "18") (pinfunction "18_18") (pintype "passive"))
      (node (ref "J5") (pin "19") (pinfunction "19_19") (pintype "passive"))
      (node (ref "J5") (pin "20") (pinfunction "20_20") (pintype "passive"))
      (node (ref "J6") (pin "09") (pinfunction "09_09") (pintype "passive"))
      (node (ref "J6") (pin "10") (pinfunction "10_10") (pintype "passive"))
      (node (ref "J6") (pin "11") (pinfunction "11_11") (pintype "passive"))
      (node (ref "J6") (pin "12") (pinfunction "12_12") (pintype "passive"))
      (node (ref "J6") (pin "13") (pinfunction "13_13") (pintype "passive"))
      (node (ref "J6") (pin "14") (pinfunction "14_14") (pintype "passive"))
      (node (ref "J6") (pin "15") (pinfunction "15_15") (pintype "passive"))
      (node (ref "J6") (pin "16") (pinfunction "16_16") (pintype "passive"))
      (node (ref "J6") (pin "17") (pinfunction "17_17") (pintype "passive"))
      (node (ref "J6") (pin "18") (pinfunction "18_18") (pintype "passive"))
      (node (ref "J6") (pin "19") (pinfunction "19_19") (pintype "passive"))
      (node (ref "J6") (pin "20") (pinfunction "20_20") (pintype "passive"))
      (node (ref "J7") (pin "09") (pinfunction "09_09") (pintype "passive"))
      (node (ref "J7") (pin "10") (pinfunction "10_10") (pintype "passive"))
      (node (ref "J7") (pin "11") (pinfunction "11_11") (pintype "passive"))
      (node (ref "J7") (pin "12") (pinfunction "12_12") (pintype "passive"))
      (node (ref "J7") (pin "13") (pinfunction "13_13") (pintype "passive"))
      (node (ref "J7") (pin "14") (pinfunction "14_14") (pintype "passive"))
      (node (ref "J7") (pin "15") (pinfunction "15_15") (pintype "passive"))
      (node (ref "J7") (pin "16") (pinfunction "16_16") (pintype "passive"))
      (node (ref "J7") (pin "17") (pinfunction "17_17") (pintype "passive"))
      (node (ref "J7") (pin "18") (pinfunction "18_18") (pintype "passive"))
      (node (ref "J7") (pin "19") (pinfunction "19_19") (pintype "passive"))
      (node (ref "J7") (pin "20") (pinfunction "20_20") (pintype "passive"))
      (node (ref "J8") (pin "09") (pinfunction "09_09") (pintype "passive"))
      (node (ref "J8") (pin "10") (pinfunction "10_10") (pintype "passive"))
      (node (ref "J8") (pin "11") (pinfunction "11_11") (pintype "passive"))
      (node (ref "J8") (pin "12") (pinfunction "12_12") (pintype "passive"))
      (node (ref "J8") (pin "13") (pinfunction "13_13") (pintype "passive"))
      (node (ref "J8") (pin "14") (pinfunction "14_14") (pintype "passive"))
      (node (ref "J8") (pin "15") (pinfunction "15_15") (pintype "passive"))
      (node (ref "J8") (pin "16") (pinfunction "16_16") (pintype "passive"))
      (node (ref "J8") (pin "17") (pinfunction "17_17") (pintype "passive"))
      (node (ref "J8") (pin "18") (pinfunction "18_18") (pintype "passive"))
      (node (ref "J8") (pin "19") (pinfunction "19_19") (pintype "passive"))
      (node (ref "J8") (pin "20") (pinfunction "20_20") (pintype "passive"))
      (node (ref "U$1") (pin "-") (pinfunction "-_-") (pintype "passive"))
    )
  )
)
